# SINS.net
KiCad netlist of a schematic drawn in EAGLE
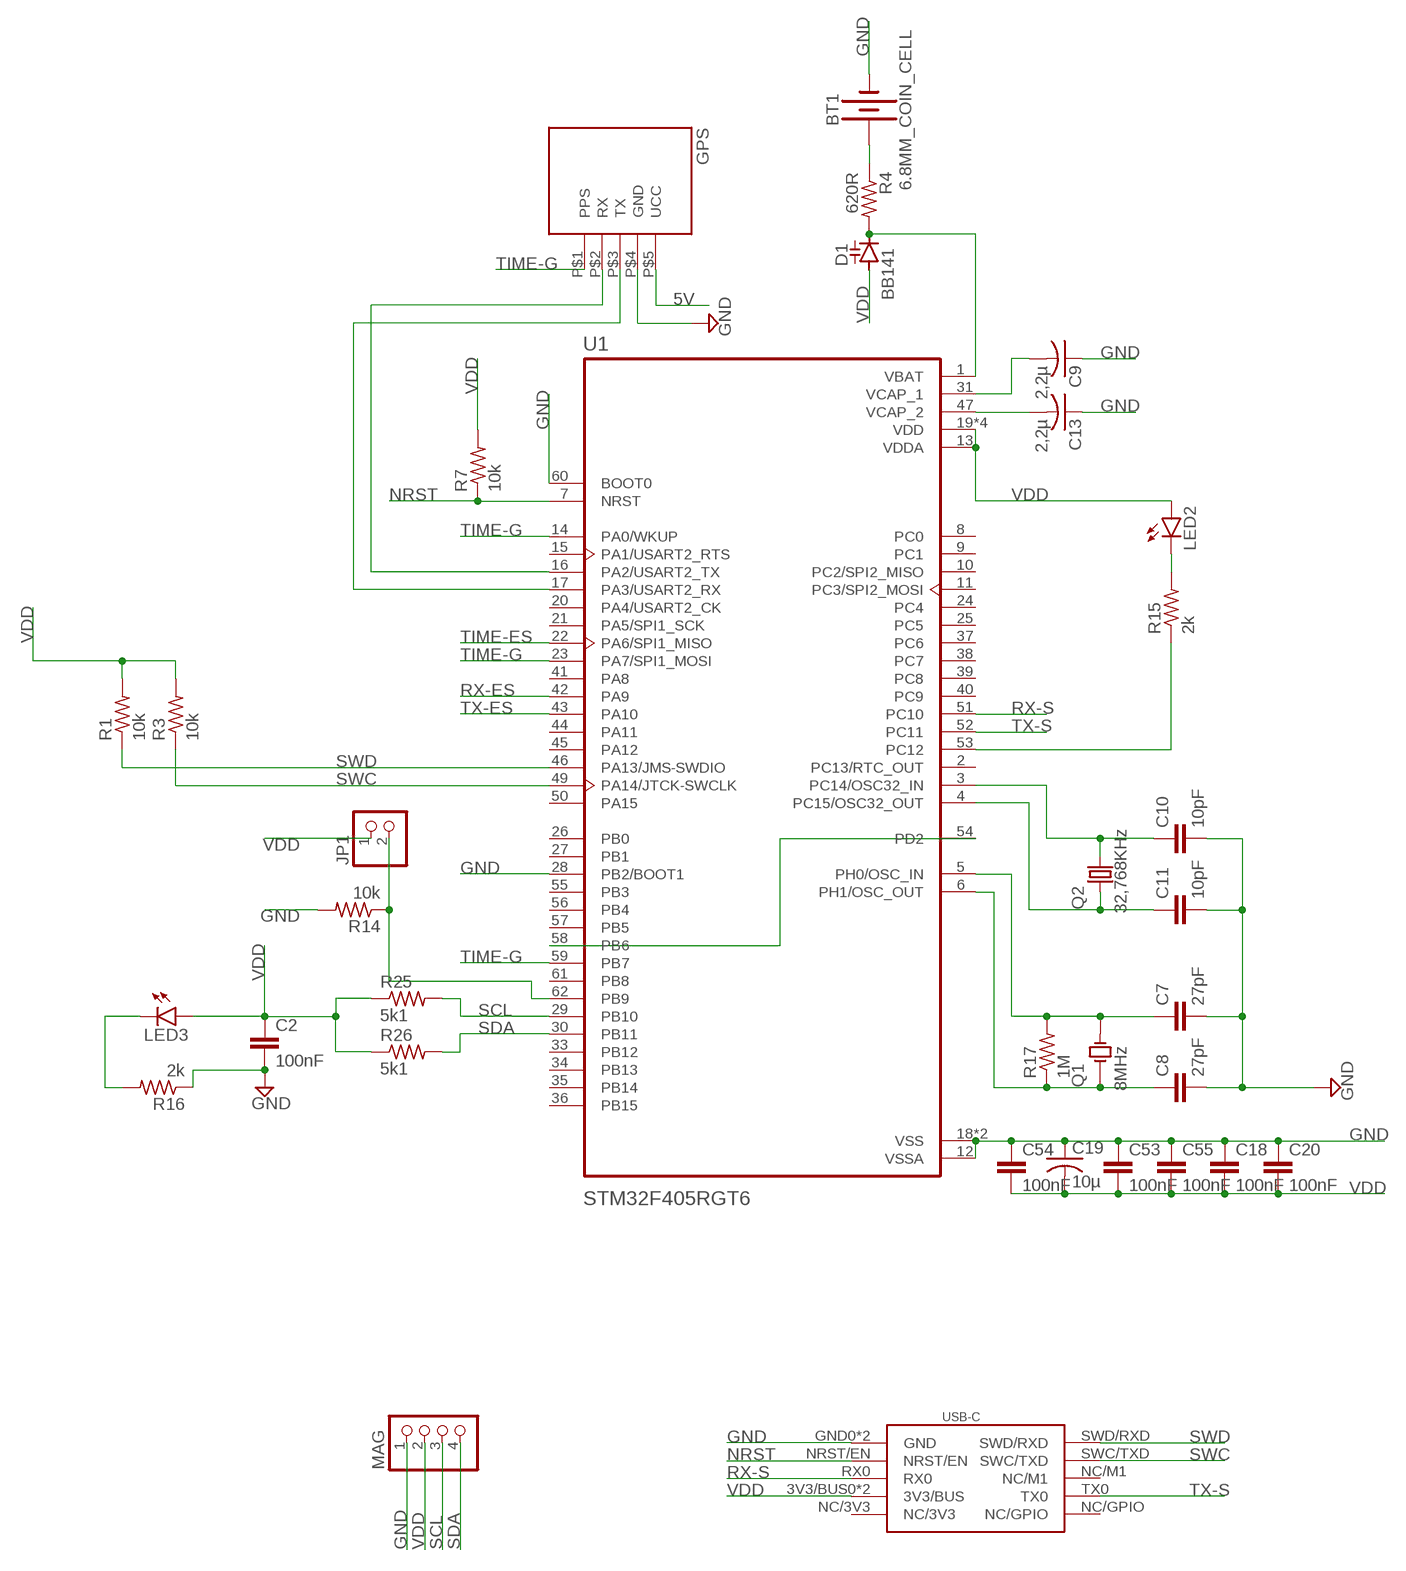
[diagram p0: schematic, sheet 1]

(export (version "E")
  (design (tool "Eeschema 10.0.6"))
  (components
    (comp (ref "BT1")
      (value "6.8MM_COIN_CELL")
      (footprint "eagle-import:BATTCON-6.8MM")
      (libsource (lib "eagle-import") (part "BATTERY-6.8MM_SMD"))
    )
    (comp (ref "C2")
      (value "100nF")
      (footprint "eagle-import:C0603")
      (libsource (lib "eagle-import") (part "C-EUC0603"))
    )
    (comp (ref "C7")
      (value "27pF")
      (footprint "eagle-import:C0603")
      (libsource (lib "eagle-import") (part "C-EUC0603"))
    )
    (comp (ref "C8")
      (value "27pF")
      (footprint "eagle-import:C0603")
      (libsource (lib "eagle-import") (part "C-EUC0603"))
    )
    (comp (ref "C9")
      (value "2,2µ")
      (footprint "eagle-import:C0603")
      (libsource (lib "eagle-import") (part "C-USC0603"))
    )
    (comp (ref "C10")
      (value "10pF")
      (footprint "eagle-import:C0603")
      (libsource (lib "eagle-import") (part "C-EUC0603"))
    )
    (comp (ref "C11")
      (value "10pF")
      (footprint "eagle-import:C0603")
      (libsource (lib "eagle-import") (part "C-EUC0603"))
    )
    (comp (ref "C13")
      (value "2,2µ")
      (footprint "eagle-import:C0603")
      (libsource (lib "eagle-import") (part "C-USC0603"))
    )
    (comp (ref "C18")
      (value "100nF")
      (footprint "eagle-import:C0603")
      (libsource (lib "eagle-import") (part "C-EUC0603"))
    )
    (comp (ref "C19")
      (value "10µ")
      (footprint "eagle-import:C1206")
      (libsource (lib "eagle-import") (part "C-USC1206"))
    )
    (comp (ref "C20")
      (value "100nF")
      (footprint "eagle-import:C0603")
      (libsource (lib "eagle-import") (part "C-EUC0603"))
    )
    (comp (ref "C53")
      (value "100nF")
      (footprint "eagle-import:C0603")
      (libsource (lib "eagle-import") (part "C-EUC0603"))
    )
    (comp (ref "C54")
      (value "100nF")
      (footprint "eagle-import:C0603")
      (libsource (lib "eagle-import") (part "C-EUC0603"))
    )
    (comp (ref "C55")
      (value "100nF")
      (footprint "eagle-import:C0603")
      (libsource (lib "eagle-import") (part "C-EUC0603"))
    )
    (comp (ref "D1")
      (value "BB141")
      (footprint "eagle-import:SOD523")
      (libsource (lib "eagle-import") (part "BB141"))
    )
    (comp (ref "GPS")
      (value "GPSNEO6M")
      (footprint "eagle-import:GPS-NEO6M")
      (libsource (lib "eagle-import") (part "GPSNEO6M"))
    )
    (comp (ref "JP1")
      (value "PINHD-1X2")
      (footprint "eagle-import:1X02")
      (libsource (lib "eagle-import") (part "PINHD-1X2"))
    )
    (comp (ref "LED2")
      (value "LEDCHIPLED_0603")
      (footprint "eagle-import:CHIPLED_0603")
      (libsource (lib "eagle-import") (part "LEDCHIPLED_0603"))
    )
    (comp (ref "LED3")
      (value "LEDCHIPLED_0603")
      (footprint "eagle-import:CHIPLED_0603")
      (libsource (lib "eagle-import") (part "LEDCHIPLED_0603"))
    )
    (comp (ref "MAG")
      (value "PINHD-1X4")
      (footprint "eagle-import:1X04")
      (libsource (lib "eagle-import") (part "PINHD-1X4"))
    )
    (comp (ref "Q1")
      (value "8MHz")
      (footprint "eagle-import:XTAL_9C-8.000MEEJ-T")
      (fields (field (name "MF") "TXC CORPORATION") (field (name "MP") "9C-8.000MEEJ-T"))
      (libsource (lib "eagle-import") (part "9C-8.000MEEJ-T"))
    )
    (comp (ref "Q2")
      (value "32,768KHz")
      (footprint "eagle-import:C005R")
      (libsource (lib "eagle-import") (part "C005R"))
    )
    (comp (ref "R1")
      (value "10k")
      (footprint "eagle-import:R0603")
      (libsource (lib "eagle-import") (part "R-US_R0603"))
    )
    (comp (ref "R3")
      (value "10k")
      (footprint "eagle-import:R0603")
      (libsource (lib "eagle-import") (part "R-US_R0603"))
    )
    (comp (ref "R4")
      (value "620R")
      (footprint "eagle-import:R0603")
      (libsource (lib "eagle-import") (part "R-US_R0603"))
    )
    (comp (ref "R7")
      (value "10k")
      (footprint "eagle-import:R0603")
      (libsource (lib "eagle-import") (part "R-US_R0603"))
    )
    (comp (ref "R14")
      (value "10k")
      (footprint "eagle-import:R0603")
      (libsource (lib "eagle-import") (part "R-US_R0603"))
    )
    (comp (ref "R15")
      (value "2k")
      (footprint "eagle-import:R0603")
      (libsource (lib "eagle-import") (part "R-US_R0603"))
    )
    (comp (ref "R16")
      (value "2k")
      (footprint "eagle-import:R0603")
      (libsource (lib "eagle-import") (part "R-US_R0603"))
    )
    (comp (ref "R17")
      (value "1M")
      (footprint "eagle-import:R0603")
      (libsource (lib "eagle-import") (part "R-US_R0603"))
    )
    (comp (ref "R25")
      (value "5k1")
      (footprint "eagle-import:R0603")
      (libsource (lib "eagle-import") (part "R-US_R0603"))
    )
    (comp (ref "R26")
      (value "5k1")
      (footprint "eagle-import:R0603")
      (libsource (lib "eagle-import") (part "R-US_R0603"))
    )
    (comp (ref "U$4")
      (value "USB-C")
      (footprint "eagle-import:USB-C")
      (libsource (lib "eagle-import") (part "USB-C"))
    )
    (comp (ref "U1")
      (value "STM32F405RGT6")
      (footprint "eagle-import:QFP50P1200X1200X160-64N")
      (fields (field (name "DIGI-KEY_PART_NUMBER") "497-11767-ND") (field (name "MF") "STMicroelectronics"))
      (libsource (lib "eagle-import") (part "STM32F405RGT6"))
    )
  )
  (nets
    (net (code "1") (name "/5V") (class "Default")
      (node (ref "GPS") (pin "P$5") (pinfunction "UCC_P$5") (pintype "bidirectional"))
    )
    (net (code "2") (name "/NRST") (class "Default")
      (node (ref "R7") (pin "1") (pinfunction "1_1") (pintype "passive"))
      (node (ref "U$4") (pin "NRST/EN") (pinfunction "NRST/EN_NRST/EN") (pintype "bidirectional"))
      (node (ref "U1") (pin "7") (pinfunction "NRST_7") (pintype "bidirectional"))
    )
    (net (code "3") (name "/RX-ES") (class "Default")
      (node (ref "U1") (pin "42") (pinfunction "PA9_42") (pintype "bidirectional"))
    )
    (net (code "4") (name "/RX-S") (class "Default")
      (node (ref "U$4") (pin "RX0") (pinfunction "RX0_RX0") (pintype "bidirectional"))
      (node (ref "U1") (pin "51") (pinfunction "PC10_51") (pintype "bidirectional"))
    )
    (net (code "5") (name "/SCL") (class "Default")
      (node (ref "MAG") (pin "3") (pinfunction "3_3") (pintype "passive"))
      (node (ref "R25") (pin "2") (pinfunction "2_2") (pintype "passive"))
      (node (ref "U1") (pin "29") (pinfunction "PB10_29") (pintype "bidirectional"))
    )
    (net (code "6") (name "/SDA") (class "Default")
      (node (ref "MAG") (pin "4") (pinfunction "4_4") (pintype "passive"))
      (node (ref "R26") (pin "2") (pinfunction "2_2") (pintype "passive"))
      (node (ref "U1") (pin "30") (pinfunction "PB11_30") (pintype "bidirectional"))
    )
    (net (code "7") (name "/SWC") (class "Default")
      (node (ref "R3") (pin "1") (pinfunction "1_1") (pintype "passive"))
      (node (ref "U$4") (pin "SWC/TXD") (pinfunction "SWC/TXD_SWC/TXD") (pintype "bidirectional"))
      (node (ref "U1") (pin "49") (pinfunction "PA14/JTCK-SWCLK_49") (pintype "bidirectional"))
    )
    (net (code "8") (name "/SWD") (class "Default")
      (node (ref "R1") (pin "1") (pinfunction "1_1") (pintype "passive"))
      (node (ref "U$4") (pin "SWD/RXD") (pinfunction "SWD/RXD_SWD/RXD") (pintype "bidirectional"))
      (node (ref "U1") (pin "46") (pinfunction "PA13/JMS-SWDIO_46") (pintype "bidirectional"))
    )
    (net (code "9") (name "/TIME-ES") (class "Default")
      (node (ref "U1") (pin "22") (pinfunction "PA6/SPI1_MISO_22") (pintype "bidirectional"))
    )
    (net (code "10") (name "/TIME-G") (class "Default")
      (node (ref "GPS") (pin "P$1") (pinfunction "PPS_P$1") (pintype "bidirectional"))
      (node (ref "U1") (pin "14") (pinfunction "PA0/WKUP_14") (pintype "bidirectional"))
      (node (ref "U1") (pin "23") (pinfunction "PA7/SPI1_MOSI_23") (pintype "bidirectional"))
      (node (ref "U1") (pin "59") (pinfunction "PB7_59") (pintype "bidirectional"))
    )
    (net (code "11") (name "/TX-ES") (class "Default")
      (node (ref "U1") (pin "43") (pinfunction "PA10_43") (pintype "bidirectional"))
    )
    (net (code "12") (name "/TX-S") (class "Default")
      (node (ref "U$4") (pin "TX0") (pinfunction "TX0_TX0") (pintype "bidirectional"))
      (node (ref "U1") (pin "52") (pinfunction "PC11_52") (pintype "bidirectional"))
    )
    (net (code "13") (name "/VDD") (class "Default")
      (node (ref "C18") (pin "2") (pinfunction "2_2") (pintype "passive"))
      (node (ref "C19") (pin "2") (pinfunction "2_2") (pintype "passive"))
      (node (ref "C2") (pin "1") (pinfunction "1_1") (pintype "passive"))
      (node (ref "C20") (pin "2") (pinfunction "2_2") (pintype "passive"))
      (node (ref "C53") (pin "2") (pinfunction "2_2") (pintype "passive"))
      (node (ref "C54") (pin "2") (pinfunction "2_2") (pintype "passive"))
      (node (ref "C55") (pin "2") (pinfunction "2_2") (pintype "passive"))
      (node (ref "D1") (pin "A") (pinfunction "A_A") (pintype "passive"))
      (node (ref "JP1") (pin "1") (pinfunction "1_1") (pintype "passive"))
      (node (ref "LED2") (pin "A") (pinfunction "A_A") (pintype "passive"))
      (node (ref "LED3") (pin "A") (pinfunction "A_A") (pintype "passive"))
      (node (ref "MAG") (pin "2") (pinfunction "2_2") (pintype "passive"))
      (node (ref "R1") (pin "2") (pinfunction "2_2") (pintype "passive"))
      (node (ref "R25") (pin "1") (pinfunction "1_1") (pintype "passive"))
      (node (ref "R26") (pin "1") (pinfunction "1_1") (pintype "passive"))
      (node (ref "R3") (pin "2") (pinfunction "2_2") (pintype "passive"))
      (node (ref "R7") (pin "2") (pinfunction "2_2") (pintype "passive"))
      (node (ref "U$4") (pin "3V3/BUS0") (pinfunction "3V3/BUS_3V3/BUS0") (pintype "bidirectional"))
      (node (ref "U$4") (pin "3V3/BUS1") (pinfunction "3V3/BUS_3V3/BUS1") (pintype "bidirectional"))
      (node (ref "U1") (pin "13") (pinfunction "VDDA_13") (pintype "power_in"))
      (node (ref "U1") (pin "19") (pinfunction "VDD_19") (pintype "power_in"))
      (node (ref "U1") (pin "32") (pinfunction "VDD_32") (pintype "power_in"))
      (node (ref "U1") (pin "48") (pinfunction "VDD_48") (pintype "power_in"))
      (node (ref "U1") (pin "64") (pinfunction "VDD_64") (pintype "power_in"))
    )
    (net (code "14") (name "GND") (class "Default")
      (node (ref "BT1") (pin "-") (pinfunction "-_-") (pintype "power_in"))
      (node (ref "C10") (pin "2") (pinfunction "2_2") (pintype "passive"))
      (node (ref "C11") (pin "2") (pinfunction "2_2") (pintype "passive"))
      (node (ref "C13") (pin "1") (pinfunction "1_1") (pintype "passive"))
      (node (ref "C18") (pin "1") (pinfunction "1_1") (pintype "passive"))
      (node (ref "C19") (pin "1") (pinfunction "1_1") (pintype "passive"))
      (node (ref "C2") (pin "2") (pinfunction "2_2") (pintype "passive"))
      (node (ref "C20") (pin "1") (pinfunction "1_1") (pintype "passive"))
      (node (ref "C53") (pin "1") (pinfunction "1_1") (pintype "passive"))
      (node (ref "C54") (pin "1") (pinfunction "1_1") (pintype "passive"))
      (node (ref "C55") (pin "1") (pinfunction "1_1") (pintype "passive"))
      (node (ref "C7") (pin "2") (pinfunction "2_2") (pintype "passive"))
      (node (ref "C8") (pin "2") (pinfunction "2_2") (pintype "passive"))
      (node (ref "C9") (pin "1") (pinfunction "1_1") (pintype "passive"))
      (node (ref "GPS") (pin "P$4") (pinfunction "GND_P$4") (pintype "bidirectional"))
      (node (ref "MAG") (pin "1") (pinfunction "1_1") (pintype "passive"))
      (node (ref "R14") (pin "2") (pinfunction "2_2") (pintype "passive"))
      (node (ref "R16") (pin "1") (pinfunction "1_1") (pintype "passive"))
      (node (ref "U$4") (pin "GND0") (pinfunction "GND_GND0") (pintype "bidirectional"))
      (node (ref "U$4") (pin "GND1") (pinfunction "GND_GND1") (pintype "bidirectional"))
      (node (ref "U1") (pin "12") (pinfunction "VSSA_12") (pintype "power_in"))
      (node (ref "U1") (pin "18") (pinfunction "VSS_18") (pintype "power_in"))
      (node (ref "U1") (pin "28") (pinfunction "PB2/BOOT1_28") (pintype "bidirectional"))
      (node (ref "U1") (pin "60") (pinfunction "BOOT0_60") (pintype "bidirectional"))
      (node (ref "U1") (pin "63") (pinfunction "VSS_63") (pintype "power_in"))
    )
    (net (code "15") (name "Net-(BT1-Pad+)") (class "Default")
      (node (ref "BT1") (pin "+") (pinfunction "+_+") (pintype "power_in"))
      (node (ref "R4") (pin "1") (pinfunction "1_1") (pintype "passive"))
    )
    (net (code "16") (name "Net-(GPS-RX)") (class "Default")
      (node (ref "GPS") (pin "P$2") (pinfunction "RX_P$2") (pintype "bidirectional"))
      (node (ref "U1") (pin "16") (pinfunction "PA2/USART2_TX_16") (pintype "bidirectional"))
    )
    (net (code "17") (name "Net-(GPS-TX)") (class "Default")
      (node (ref "GPS") (pin "P$3") (pinfunction "TX_P$3") (pintype "bidirectional"))
      (node (ref "U1") (pin "17") (pinfunction "PA3/USART2_RX_17") (pintype "bidirectional"))
    )
    (net (code "18") (name "Net-(LED2-PadC)") (class "Default")
      (node (ref "LED2") (pin "C") (pinfunction "C_C") (pintype "passive"))
      (node (ref "R15") (pin "2") (pinfunction "2_2") (pintype "passive"))
    )
    (net (code "19") (name "Net-(LED3-PadC)") (class "Default")
      (node (ref "LED3") (pin "C") (pinfunction "C_C") (pintype "passive"))
      (node (ref "R16") (pin "2") (pinfunction "2_2") (pintype "passive"))
    )
    (net (code "20") (name "Net-(Q2-1)") (class "Default")
      (node (ref "C11") (pin "1") (pinfunction "1_1") (pintype "passive"))
      (node (ref "Q2") (pin "P$1") (pinfunction "1_P$1") (pintype "passive"))
      (node (ref "U1") (pin "4") (pinfunction "PC15/OSC32_OUT_4") (pintype "bidirectional"))
    )
    (net (code "21") (name "Net-(Q2-2)") (class "Default")
      (node (ref "C10") (pin "1") (pinfunction "1_1") (pintype "passive"))
      (node (ref "Q2") (pin "P$2") (pinfunction "2_P$2") (pintype "passive"))
      (node (ref "U1") (pin "3") (pinfunction "PC14/OSC32_IN_3") (pintype "bidirectional"))
    )
    (net (code "22") (name "Net-(U1-PB6)") (class "Default")
      (node (ref "U1") (pin "54") (pinfunction "PD2_54") (pintype "bidirectional"))
      (node (ref "U1") (pin "58") (pinfunction "PB6_58") (pintype "bidirectional"))
    )
    (net (code "23") (name "Net-(U1-PB9)") (class "Default")
      (node (ref "JP1") (pin "2") (pinfunction "2_2") (pintype "passive"))
      (node (ref "R14") (pin "1") (pinfunction "1_1") (pintype "passive"))
      (node (ref "U1") (pin "62") (pinfunction "PB9_62") (pintype "bidirectional"))
    )
    (net (code "24") (name "Net-(U1-PC12)") (class "Default")
      (node (ref "R15") (pin "1") (pinfunction "1_1") (pintype "passive"))
      (node (ref "U1") (pin "53") (pinfunction "PC12_53") (pintype "bidirectional"))
    )
    (net (code "25") (name "Net-(U1-PH0{slash}OSC_IN)") (class "Default")
      (node (ref "C7") (pin "1") (pinfunction "1_1") (pintype "passive"))
      (node (ref "Q1") (pin "2") (pinfunction "2_2") (pintype "passive"))
      (node (ref "R17") (pin "2") (pinfunction "2_2") (pintype "passive"))
      (node (ref "U1") (pin "5") (pinfunction "PH0/OSC_IN_5") (pintype "bidirectional"))
    )
    (net (code "26") (name "Net-(U1-PH1{slash}OSC_OUT)") (class "Default")
      (node (ref "C8") (pin "1") (pinfunction "1_1") (pintype "passive"))
      (node (ref "Q1") (pin "1") (pinfunction "1_1") (pintype "passive"))
      (node (ref "R17") (pin "1") (pinfunction "1_1") (pintype "passive"))
      (node (ref "U1") (pin "6") (pinfunction "PH1/OSC_OUT_6") (pintype "bidirectional"))
    )
    (net (code "27") (name "Net-(U1-VBAT)") (class "Default")
      (node (ref "D1") (pin "C") (pinfunction "C_C") (pintype "passive"))
      (node (ref "R4") (pin "2") (pinfunction "2_2") (pintype "passive"))
      (node (ref "U1") (pin "1") (pinfunction "VBAT_1") (pintype "power_in"))
    )
    (net (code "28") (name "Net-(U1-VCAP_1)") (class "Default")
      (node (ref "C9") (pin "2") (pinfunction "2_2") (pintype "passive"))
      (node (ref "U1") (pin "31") (pinfunction "VCAP_1_31") (pintype "power_in"))
    )
    (net (code "29") (name "Net-(U1-VCAP_2)") (class "Default")
      (node (ref "C13") (pin "2") (pinfunction "2_2") (pintype "passive"))
      (node (ref "U1") (pin "47") (pinfunction "VCAP_2_47") (pintype "power_in"))
    )
    (net (code "30") (name "unconnected-(U$4-PadNC{slash}3V3)") (class "Default")
      (node (ref "U$4") (pin "NC/3V3") (pinfunction "NC/3V3_NC/3V3") (pintype "bidirectional"))
    )
    (net (code "31") (name "unconnected-(U$4-PadNC{slash}GPIO)") (class "Default")
      (node (ref "U$4") (pin "NC/GPIO") (pinfunction "NC/GPIO_NC/GPIO") (pintype "bidirectional"))
    )
    (net (code "32") (name "unconnected-(U$4-PadNC{slash}M1)") (class "Default")
      (node (ref "U$4") (pin "NC/M1") (pinfunction "NC/M1_NC/M1") (pintype "bidirectional"))
    )
    (net (code "33") (name "unconnected-(U1-PA1{slash}USART2_RTS-Pad15)") (class "Default")
      (node (ref "U1") (pin "15") (pinfunction "PA1/USART2_RTS_15") (pintype "bidirectional"))
    )
    (net (code "34") (name "unconnected-(U1-PA4{slash}USART2_CK-Pad20)") (class "Default")
      (node (ref "U1") (pin "20") (pinfunction "PA4/USART2_CK_20") (pintype "bidirectional"))
    )
    (net (code "35") (name "unconnected-(U1-PA5{slash}SPI1_SCK-Pad21)") (class "Default")
      (node (ref "U1") (pin "21") (pinfunction "PA5/SPI1_SCK_21") (pintype "bidirectional"))
    )
    (net (code "36") (name "unconnected-(U1-PA8-Pad41)") (class "Default")
      (node (ref "U1") (pin "41") (pinfunction "PA8_41") (pintype "bidirectional"))
    )
    (net (code "37") (name "unconnected-(U1-PA11-Pad44)") (class "Default")
      (node (ref "U1") (pin "44") (pinfunction "PA11_44") (pintype "bidirectional"))
    )
    (net (code "38") (name "unconnected-(U1-PA12-Pad45)") (class "Default")
      (node (ref "U1") (pin "45") (pinfunction "PA12_45") (pintype "bidirectional"))
    )
    (net (code "39") (name "unconnected-(U1-PA15-Pad50)") (class "Default")
      (node (ref "U1") (pin "50") (pinfunction "PA15_50") (pintype "bidirectional"))
    )
    (net (code "40") (name "unconnected-(U1-PB0-Pad26)") (class "Default")
      (node (ref "U1") (pin "26") (pinfunction "PB0_26") (pintype "bidirectional"))
    )
    (net (code "41") (name "unconnected-(U1-PB1-Pad27)") (class "Default")
      (node (ref "U1") (pin "27") (pinfunction "PB1_27") (pintype "bidirectional"))
    )
    (net (code "42") (name "unconnected-(U1-PB3-Pad55)") (class "Default")
      (node (ref "U1") (pin "55") (pinfunction "PB3_55") (pintype "bidirectional"))
    )
    (net (code "43") (name "unconnected-(U1-PB4-Pad56)") (class "Default")
      (node (ref "U1") (pin "56") (pinfunction "PB4_56") (pintype "bidirectional"))
    )
    (net (code "44") (name "unconnected-(U1-PB5-Pad57)") (class "Default")
      (node (ref "U1") (pin "57") (pinfunction "PB5_57") (pintype "bidirectional"))
    )
    (net (code "45") (name "unconnected-(U1-PB8-Pad61)") (class "Default")
      (node (ref "U1") (pin "61") (pinfunction "PB8_61") (pintype "bidirectional"))
    )
    (net (code "46") (name "unconnected-(U1-PB12-Pad33)") (class "Default")
      (node (ref "U1") (pin "33") (pinfunction "PB12_33") (pintype "bidirectional"))
    )
    (net (code "47") (name "unconnected-(U1-PB13-Pad34)") (class "Default")
      (node (ref "U1") (pin "34") (pinfunction "PB13_34") (pintype "bidirectional"))
    )
    (net (code "48") (name "unconnected-(U1-PB14-Pad35)") (class "Default")
      (node (ref "U1") (pin "35") (pinfunction "PB14_35") (pintype "bidirectional"))
    )
    (net (code "49") (name "unconnected-(U1-PB15-Pad36)") (class "Default")
      (node (ref "U1") (pin "36") (pinfunction "PB15_36") (pintype "bidirectional"))
    )
    (net (code "50") (name "unconnected-(U1-PC0-Pad8)") (class "Default")
      (node (ref "U1") (pin "8") (pinfunction "PC0_8") (pintype "bidirectional"))
    )
    (net (code "51") (name "unconnected-(U1-PC1-Pad9)") (class "Default")
      (node (ref "U1") (pin "9") (pinfunction "PC1_9") (pintype "bidirectional"))
    )
    (net (code "52") (name "unconnected-(U1-PC2{slash}SPI2_MISO-Pad10)") (class "Default")
      (node (ref "U1") (pin "10") (pinfunction "PC2/SPI2_MISO_10") (pintype "bidirectional"))
    )
    (net (code "53") (name "unconnected-(U1-PC3{slash}SPI2_MOSI-Pad11)") (class "Default")
      (node (ref "U1") (pin "11") (pinfunction "PC3/SPI2_MOSI_11") (pintype "bidirectional"))
    )
    (net (code "54") (name "unconnected-(U1-PC4-Pad24)") (class "Default")
      (node (ref "U1") (pin "24") (pinfunction "PC4_24") (pintype "bidirectional"))
    )
    (net (code "55") (name "unconnected-(U1-PC5-Pad25)") (class "Default")
      (node (ref "U1") (pin "25") (pinfunction "PC5_25") (pintype "bidirectional"))
    )
    (net (code "56") (name "unconnected-(U1-PC6-Pad37)") (class "Default")
      (node (ref "U1") (pin "37") (pinfunction "PC6_37") (pintype "bidirectional"))
    )
    (net (code "57") (name "unconnected-(U1-PC7-Pad38)") (class "Default")
      (node (ref "U1") (pin "38") (pinfunction "PC7_38") (pintype "bidirectional"))
    )
    (net (code "58") (name "unconnected-(U1-PC8-Pad39)") (class "Default")
      (node (ref "U1") (pin "39") (pinfunction "PC8_39") (pintype "bidirectional"))
    )
    (net (code "59") (name "unconnected-(U1-PC9-Pad40)") (class "Default")
      (node (ref "U1") (pin "40") (pinfunction "PC9_40") (pintype "bidirectional"))
    )
    (net (code "60") (name "unconnected-(U1-PC13{slash}RTC_OUT-Pad2)") (class "Default")
      (node (ref "U1") (pin "2") (pinfunction "PC13/RTC_OUT_2") (pintype "bidirectional"))
    )
  )
)
